# bms_EMBEDDED_R00.net
KiCad netlist of a schematic drawn in Altium Designer
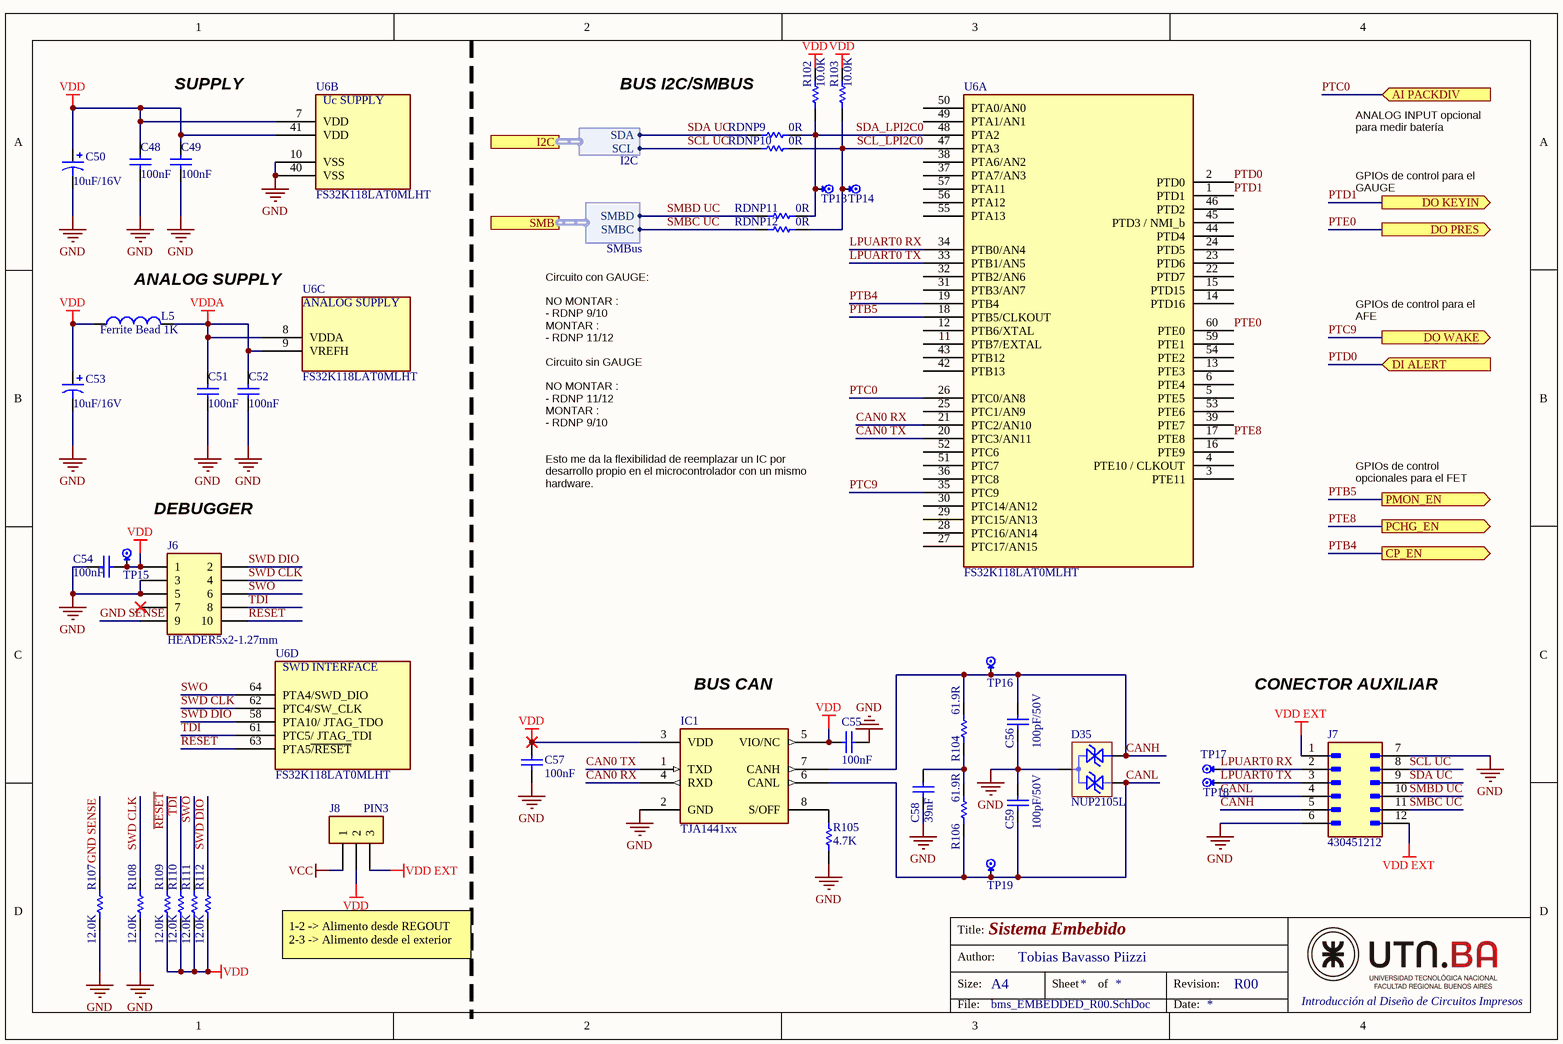
[diagram p0: bms_EMBEDDED_R00.SchDoc]

(export (version "E")
  (design (tool "Eeschema 10.0.6"))
  (components
    (comp (ref "C48")
      (value "100nF")
      (footprint "C0603")
      (description "Capacitor")
      (libsource (lib "capacitors") (part "Cap 0603"))
    )
    (comp (ref "C49")
      (value "100nF")
      (footprint "C0603")
      (description "Capacitor")
      (libsource (lib "capacitors") (part "Cap 0603"))
    )
    (comp (ref "C50")
      (value "10uF/16V")
      (footprint "1206 Cap Tant")
      (description "Polarized Capacitor Tantalium")
      (libsource (lib "capacitors") (part "Cap Pol Tantalio"))
    )
    (comp (ref "C51")
      (value "100nF")
      (footprint "C0603")
      (description "Capacitor")
      (libsource (lib "capacitors") (part "Cap 0603"))
    )
    (comp (ref "C52")
      (value "100nF")
      (footprint "C0603")
      (description "Capacitor")
      (libsource (lib "capacitors") (part "Cap 0603"))
    )
    (comp (ref "C53")
      (value "10uF/16V")
      (footprint "1206 Cap Tant")
      (description "Polarized Capacitor Tantalium")
      (libsource (lib "capacitors") (part "Cap Pol Tantalio"))
    )
    (comp (ref "C54")
      (value "100nF")
      (footprint "C0603")
      (description "Capacitor")
      (libsource (lib "capacitors") (part "Cap 0603"))
    )
    (comp (ref "C55")
      (value "100nF")
      (footprint "C0603")
      (description "Capacitor")
      (libsource (lib "capacitors") (part "Cap 0603"))
    )
    (comp (ref "C56")
      (value "100pF/50V")
      (footprint "C0603")
      (description "Capacitor")
      (libsource (lib "capacitors") (part "Cap 0603"))
    )
    (comp (ref "C57")
      (value "100nF")
      (footprint "C0603")
      (description "Capacitor")
      (libsource (lib "capacitors") (part "Cap 0603"))
    )
    (comp (ref "C58")
      (value "39nF")
      (footprint "C0603")
      (description "Capacitor")
      (libsource (lib "capacitors") (part "Cap 0603"))
    )
    (comp (ref "C59")
      (value "100pF/50V")
      (footprint "C0603")
      (description "Capacitor")
      (libsource (lib "capacitors") (part "Cap 0603"))
    )
    (comp (ref "D35")
      (value "NUP2105L")
      (footprint "SOT-23")
      (description "Dual Line CAN Bus Protector TVS DIODE 24VWM 44VC SOT23-3")
      (libsource (lib "diodes") (part "NUP2105L"))
    )
    (comp (ref "IC1")
      (value "TJA1441xx")
      (footprint "SOIC8")
      (description "High-speed CAN transceiver")
      (libsource (lib "integrated_circuits") (part "TJA1441xx"))
    )
    (comp (ref "J6")
      (value "HEADER5x2-1.27mm")
      (footprint "PAD10-2X05-HH")
      (description "PAD10-2X05-HH")
      (libsource (lib "connectors") (part "HEADER5x2-1.27mm"))
    )
    (comp (ref "J7")
      (value "430451212")
      (footprint "MOLEX_430451212")
      (description "Micro-Fit 3.0 43045\r\nCONN HEADER VERT 12POS 3MM")
      (fields (field (name "MP") "430451012"))
      (libsource (lib "connectors") (part "430451212"))
    )
    (comp (ref "J8") (value "PIN3") (footprint "SIP3") (libsource (lib "connectors") (part "PIN3")))
    (comp (ref "L5")
      (value "Ferrite Bead 1K")
      (footprint "0603 FB")
      (description "BLM18KG102SN1D 1K")
      (libsource (lib "inductors") (part "BLM18KG102SN1D"))
    )
    (comp (ref "R102")
      (value "10.0K")
      (footprint "R0603")
      (description "Resistor")
      (libsource (lib "resistors") (part "Res"))
    )
    (comp (ref "R103")
      (value "10.0K")
      (footprint "R0603")
      (description "Resistor")
      (libsource (lib "resistors") (part "Res"))
    )
    (comp (ref "R104")
      (value "61.9R")
      (footprint "R0603")
      (description "Resistor")
      (libsource (lib "resistors") (part "Res"))
    )
    (comp (ref "R105")
      (value "4.7K")
      (footprint "R0603")
      (description "Resistor")
      (libsource (lib "resistors") (part "Res"))
    )
    (comp (ref "R106")
      (value "61.9R")
      (footprint "R0603")
      (description "Resistor")
      (libsource (lib "resistors") (part "Res"))
    )
    (comp (ref "R107")
      (value "12.0K")
      (footprint "R0603")
      (description "Resistor")
      (libsource (lib "resistors") (part "Res"))
    )
    (comp (ref "R108")
      (value "12.0K")
      (footprint "R0603")
      (description "Resistor")
      (libsource (lib "resistors") (part "Res"))
    )
    (comp (ref "R109")
      (value "12.0K")
      (footprint "R0603")
      (description "Resistor")
      (libsource (lib "resistors") (part "Res"))
    )
    (comp (ref "R110")
      (value "12.0K")
      (footprint "R0603")
      (description "Resistor")
      (libsource (lib "resistors") (part "Res"))
    )
    (comp (ref "R111")
      (value "12.0K")
      (footprint "R0603")
      (description "Resistor")
      (libsource (lib "resistors") (part "Res"))
    )
    (comp (ref "R112")
      (value "12.0K")
      (footprint "R0603")
      (description "Resistor")
      (libsource (lib "resistors") (part "Res"))
    )
    (comp (ref "RDNP9")
      (value "0R")
      (footprint "R0603")
      (description "Resistor")
      (libsource (lib "resistors") (part "Res"))
    )
    (comp (ref "RDNP10")
      (value "0R")
      (footprint "R0603")
      (description "Resistor")
      (libsource (lib "resistors") (part "Res"))
    )
    (comp (ref "RDNP11")
      (value "0R")
      (footprint "R0603")
      (description "Resistor")
      (libsource (lib "resistors") (part "Res"))
    )
    (comp (ref "RDNP12")
      (value "0R")
      (footprint "R0603")
      (description "Resistor")
      (libsource (lib "resistors") (part "Res"))
    )
    (comp (ref "TP13")
      (value "Test Point")
      (footprint "TEST POINT SMD 1")
      (libsource (lib "connectors") (part "Test Point"))
    )
    (comp (ref "TP14")
      (value "Test Point")
      (footprint "TEST POINT SMD 1")
      (libsource (lib "connectors") (part "Test Point"))
    )
    (comp (ref "TP15")
      (value "Test Point")
      (footprint "TEST POINT SMD 1")
      (libsource (lib "connectors") (part "Test Point"))
    )
    (comp (ref "TP16")
      (value "Test Point")
      (footprint "TEST POINT SMD 1")
      (libsource (lib "connectors") (part "Test Point"))
    )
    (comp (ref "TP17")
      (value "Test Point")
      (footprint "TEST POINT SMD 1")
      (libsource (lib "connectors") (part "Test Point"))
    )
    (comp (ref "TP18")
      (value "Test Point")
      (footprint "TEST POINT SMD 1")
      (libsource (lib "connectors") (part "Test Point"))
    )
    (comp (ref "TP19")
      (value "Test Point")
      (footprint "TEST POINT SMD 1")
      (libsource (lib "connectors") (part "Test Point"))
    )
    (comp (ref "U6")
      (value "FS32K118LAT0MLHT")
      (footprint "LQFP64-NXP")
      (libsource (lib "nxp") (part "FS32K118LAT0MLHT"))
    )
  )
  (nets
    (net (code "3") (name "/CAN0 RX") (class "Default")
      (node (ref "IC1") (pin "4") (pinfunction "RXD_4") (pintype "output"))
      (node (ref "U6") (pin "21") (pinfunction "PTC2/AN10_21") (pintype "passive"))
    )
    (net (code "4") (name "/CAN0 TX") (class "Default")
      (node (ref "IC1") (pin "1") (pinfunction "TXD_1") (pintype "input"))
      (node (ref "U6") (pin "20") (pinfunction "PTC3/AN11_20") (pintype "passive"))
    )
    (net (code "5") (name "/CANH") (class "Default")
      (node (ref "C56") (pin "2") (pinfunction "2_2") (pintype "passive"))
      (node (ref "D35") (pin "1") (pinfunction "1_1") (pintype "passive"))
      (node (ref "IC1") (pin "7") (pinfunction "CANH_7") (pintype "output"))
      (node (ref "J7") (pin "5") (pinfunction "5_5") (pintype "passive"))
      (node (ref "R104") (pin "2") (pinfunction "2_2") (pintype "passive"))
      (node (ref "TP16") (pin "1") (pinfunction "1_1") (pintype "passive"))
    )
    (net (code "6") (name "/CANL") (class "Default")
      (node (ref "C59") (pin "1") (pinfunction "1_1") (pintype "passive"))
      (node (ref "D35") (pin "2") (pinfunction "2_2") (pintype "passive"))
      (node (ref "IC1") (pin "6") (pinfunction "CANL_6") (pintype "output"))
      (node (ref "J7") (pin "4") (pinfunction "4_4") (pintype "passive"))
      (node (ref "R106") (pin "1") (pinfunction "1_1") (pintype "passive"))
      (node (ref "TP19") (pin "1") (pinfunction "1_1") (pintype "passive"))
    )
    (net (code "7") (name "/GND SENSE") (class "Default")
      (node (ref "J6") (pin "9") (pinfunction "9_9") (pintype "passive"))
      (node (ref "R107") (pin "1") (pinfunction "1_1") (pintype "passive"))
    )
    (net (code "8") (name "/LPUART0 RX") (class "Default")
      (node (ref "J7") (pin "2") (pinfunction "2_2") (pintype "passive"))
      (node (ref "TP17") (pin "1") (pinfunction "1_1") (pintype "passive"))
      (node (ref "U6") (pin "34") (pinfunction "PTB0/AN4_34") (pintype "passive"))
    )
    (net (code "9") (name "/LPUART0 TX") (class "Default")
      (node (ref "J7") (pin "3") (pinfunction "3_3") (pintype "passive"))
      (node (ref "TP18") (pin "1") (pinfunction "1_1") (pintype "passive"))
      (node (ref "U6") (pin "33") (pinfunction "PTB1/AN5_33") (pintype "passive"))
    )
    (net (code "10") (name "/PTB4") (class "Default")
      (node (ref "U6") (pin "19") (pinfunction "PTB4_19") (pintype "passive"))
    )
    (net (code "11") (name "/PTB5") (class "Default")
      (node (ref "U6") (pin "18") (pinfunction "PTB5/CLKOUT_18") (pintype "passive"))
    )
    (net (code "12") (name "/PTC0") (class "Default")
      (node (ref "U6") (pin "26") (pinfunction "PTC0/AN8_26") (pintype "passive"))
    )
    (net (code "13") (name "/PTC9") (class "Default")
      (node (ref "U6") (pin "35") (pinfunction "PTC9_35") (pintype "passive"))
    )
    (net (code "14") (name "/PTD0") (class "Default")
      (node (ref "U6") (pin "2") (pinfunction "PTD0_2") (pintype "passive"))
    )
    (net (code "15") (name "/PTD1") (class "Default")
      (node (ref "U6") (pin "1") (pinfunction "PTD1_1") (pintype "passive"))
    )
    (net (code "16") (name "/PTE0") (class "Default")
      (node (ref "U6") (pin "60") (pinfunction "PTE0_60") (pintype "passive"))
    )
    (net (code "17") (name "/PTE8") (class "Default")
      (node (ref "U6") (pin "17") (pinfunction "PTE8_17") (pintype "passive"))
    )
    (net (code "18") (name "/SCL UC") (class "Default")
      (node (ref "J7") (pin "8") (pinfunction "8_8") (pintype "passive"))
      (node (ref "RDNP10") (pin "1") (pinfunction "1_1") (pintype "passive"))
    )
    (net (code "19") (name "/SCL_LPI2C0") (class "Default")
      (node (ref "R103") (pin "2") (pinfunction "2_2") (pintype "passive"))
      (node (ref "RDNP10") (pin "2") (pinfunction "2_2") (pintype "passive"))
      (node (ref "RDNP12") (pin "2") (pinfunction "2_2") (pintype "passive"))
      (node (ref "TP14") (pin "1") (pinfunction "1_1") (pintype "passive"))
      (node (ref "U6") (pin "47") (pinfunction "PTA3_47") (pintype "passive"))
    )
    (net (code "20") (name "/SDA UC") (class "Default")
      (node (ref "J7") (pin "9") (pinfunction "9_9") (pintype "passive"))
      (node (ref "RDNP9") (pin "1") (pinfunction "1_1") (pintype "passive"))
    )
    (net (code "21") (name "/SDA_LPI2C0") (class "Default")
      (node (ref "R102") (pin "2") (pinfunction "2_2") (pintype "passive"))
      (node (ref "RDNP11") (pin "2") (pinfunction "2_2") (pintype "passive"))
      (node (ref "RDNP9") (pin "2") (pinfunction "2_2") (pintype "passive"))
      (node (ref "TP13") (pin "1") (pinfunction "1_1") (pintype "passive"))
      (node (ref "U6") (pin "48") (pinfunction "PTA2_48") (pintype "passive"))
    )
    (net (code "22") (name "/SMBC UC") (class "Default")
      (node (ref "J7") (pin "11") (pinfunction "11_11") (pintype "passive"))
      (node (ref "RDNP12") (pin "1") (pinfunction "1_1") (pintype "passive"))
    )
    (net (code "23") (name "/SMBD UC") (class "Default")
      (node (ref "J7") (pin "10") (pinfunction "10_10") (pintype "passive"))
      (node (ref "RDNP11") (pin "1") (pinfunction "1_1") (pintype "passive"))
    )
    (net (code "24") (name "/SWD CLK") (class "Default")
      (node (ref "J6") (pin "4") (pinfunction "4_4") (pintype "passive"))
      (node (ref "R108") (pin "1") (pinfunction "1_1") (pintype "passive"))
      (node (ref "U6") (pin "62") (pinfunction "PTC4/SW_CLK_62") (pintype "passive"))
    )
    (net (code "25") (name "/SWD DIO") (class "Default")
      (node (ref "J6") (pin "2") (pinfunction "2_2") (pintype "passive"))
      (node (ref "R112") (pin "1") (pinfunction "1_1") (pintype "passive"))
      (node (ref "U6") (pin "58") (pinfunction "PTA10/_JTAG_TDO_58") (pintype "passive"))
    )
    (net (code "26") (name "/SWO") (class "Default")
      (node (ref "J6") (pin "6") (pinfunction "6_6") (pintype "passive"))
      (node (ref "R111") (pin "1") (pinfunction "1_1") (pintype "passive"))
      (node (ref "U6") (pin "64") (pinfunction "PTA4/SWD_DIO_64") (pintype "passive"))
    )
    (net (code "27") (name "/TDI") (class "Default")
      (node (ref "J6") (pin "8") (pinfunction "8_8") (pintype "passive"))
      (node (ref "R110") (pin "1") (pinfunction "1_1") (pintype "passive"))
      (node (ref "U6") (pin "61") (pinfunction "PTC5/_JTAG_TDI_61") (pintype "passive"))
    )
    (net (code "30") (name "/~{RESET}") (class "Default")
      (node (ref "J6") (pin "10") (pinfunction "10_10") (pintype "passive"))
      (node (ref "R109") (pin "1") (pinfunction "1_1") (pintype "passive"))
      (node (ref "U6") (pin "63") (pinfunction "PTA5~{/RESET}_63") (pintype "passive"))
    )
    (net (code "31") (name "GND") (class "Default")
      (node (ref "C48") (pin "1") (pinfunction "1_1") (pintype "passive"))
      (node (ref "C49") (pin "1") (pinfunction "1_1") (pintype "passive"))
      (node (ref "C50") (pin "2") (pinfunction "2_2") (pintype "passive"))
      (node (ref "C51") (pin "1") (pinfunction "1_1") (pintype "passive"))
      (node (ref "C52") (pin "1") (pinfunction "1_1") (pintype "passive"))
      (node (ref "C53") (pin "2") (pinfunction "2_2") (pintype "passive"))
      (node (ref "C54") (pin "1") (pinfunction "1_1") (pintype "passive"))
      (node (ref "C55") (pin "1") (pinfunction "1_1") (pintype "passive"))
      (node (ref "C56") (pin "1") (pinfunction "1_1") (pintype "passive"))
      (node (ref "C57") (pin "2") (pinfunction "2_2") (pintype "passive"))
      (node (ref "C58") (pin "1") (pinfunction "1_1") (pintype "passive"))
      (node (ref "C59") (pin "2") (pinfunction "2_2") (pintype "passive"))
      (node (ref "D35") (pin "3") (pinfunction "3_3") (pintype "passive"))
      (node (ref "IC1") (pin "2") (pinfunction "GND_2") (pintype "power_in"))
      (node (ref "J6") (pin "3") (pinfunction "3_3") (pintype "passive"))
      (node (ref "J6") (pin "5") (pinfunction "5_5") (pintype "passive"))
      (node (ref "J7") (pin "6") (pinfunction "6_6") (pintype "passive"))
      (node (ref "J7") (pin "7") (pinfunction "7_7") (pintype "passive"))
      (node (ref "R105") (pin "1") (pinfunction "1_1") (pintype "passive"))
      (node (ref "R107") (pin "2") (pinfunction "2_2") (pintype "passive"))
      (node (ref "R108") (pin "2") (pinfunction "2_2") (pintype "passive"))
      (node (ref "U6") (pin "10") (pinfunction "VSS_10") (pintype "passive"))
      (node (ref "U6") (pin "40") (pinfunction "VSS_40") (pintype "passive"))
    )
    (net (code "32") (name "Net-(C58-Pad2)") (class "Default")
      (node (ref "C58") (pin "2") (pinfunction "2_2") (pintype "passive"))
      (node (ref "R104") (pin "1") (pinfunction "1_1") (pintype "passive"))
      (node (ref "R106") (pin "2") (pinfunction "2_2") (pintype "passive"))
    )
    (net (code "33") (name "Net-(IC1-S{slash}OFF)") (class "Default")
      (node (ref "IC1") (pin "8") (pinfunction "S/OFF_8") (pintype "passive"))
      (node (ref "R105") (pin "2") (pinfunction "2_2") (pintype "passive"))
    )
    (net (code "34") (name "VCC") (class "Default")
      (node (ref "J8") (pin "1") (pinfunction "1_1") (pintype "passive"))
    )
    (net (code "35") (name "VDD") (class "Default")
      (node (ref "C48") (pin "2") (pinfunction "2_2") (pintype "passive"))
      (node (ref "C49") (pin "2") (pinfunction "2_2") (pintype "passive"))
      (node (ref "C50") (pin "1") (pinfunction "1_1") (pintype "passive"))
      (node (ref "C53") (pin "1") (pinfunction "1_1") (pintype "passive"))
      (node (ref "C54") (pin "2") (pinfunction "2_2") (pintype "passive"))
      (node (ref "C55") (pin "2") (pinfunction "2_2") (pintype "passive"))
      (node (ref "C57") (pin "1") (pinfunction "1_1") (pintype "passive"))
      (node (ref "IC1") (pin "3") (pinfunction "VDD_3") (pintype "power_in"))
      (node (ref "IC1") (pin "5") (pinfunction "VIO/NC_5") (pintype "output"))
      (node (ref "J6") (pin "1") (pinfunction "1_1") (pintype "passive"))
      (node (ref "J8") (pin "2") (pinfunction "2_2") (pintype "passive"))
      (node (ref "L5") (pin "1") (pinfunction "1_1") (pintype "passive"))
      (node (ref "R102") (pin "1") (pinfunction "1_1") (pintype "passive"))
      (node (ref "R103") (pin "1") (pinfunction "1_1") (pintype "passive"))
      (node (ref "R109") (pin "2") (pinfunction "2_2") (pintype "passive"))
      (node (ref "R110") (pin "2") (pinfunction "2_2") (pintype "passive"))
      (node (ref "R111") (pin "2") (pinfunction "2_2") (pintype "passive"))
      (node (ref "R112") (pin "2") (pinfunction "2_2") (pintype "passive"))
      (node (ref "TP15") (pin "1") (pinfunction "1_1") (pintype "passive"))
      (node (ref "U6") (pin "41") (pinfunction "VDD_41") (pintype "passive"))
      (node (ref "U6") (pin "7") (pinfunction "VDD_7") (pintype "passive"))
    )
    (net (code "36") (name "VDD EXT") (class "Default")
      (node (ref "J7") (pin "1") (pinfunction "1_1") (pintype "passive"))
      (node (ref "J7") (pin "12") (pinfunction "12_12") (pintype "passive"))
      (node (ref "J8") (pin "3") (pinfunction "3_3") (pintype "passive"))
    )
    (net (code "37") (name "VDDA") (class "Default")
      (node (ref "C51") (pin "2") (pinfunction "2_2") (pintype "passive"))
      (node (ref "C52") (pin "2") (pinfunction "2_2") (pintype "passive"))
      (node (ref "L5") (pin "2") (pinfunction "2_2") (pintype "passive"))
      (node (ref "U6") (pin "8") (pinfunction "VDDA_8") (pintype "passive"))
      (node (ref "U6") (pin "9") (pinfunction "VREFH_9") (pintype "passive"))
    )
    (net (code "38") (name "unconnected-(J6-Pad7)") (class "Default")
      (node (ref "J6") (pin "7") (pinfunction "7_7") (pintype "passive+no_connect"))
    )
    (net (code "39") (name "unconnected-(U6A-PTA0{slash}AN0-Pad50)") (class "Default")
      (node (ref "U6") (pin "50") (pinfunction "PTA0/AN0_50") (pintype "passive"))
    )
    (net (code "40") (name "unconnected-(U6A-PTA1{slash}AN1-Pad49)") (class "Default")
      (node (ref "U6") (pin "49") (pinfunction "PTA1/AN1_49") (pintype "passive"))
    )
    (net (code "41") (name "unconnected-(U6A-PTA6{slash}AN2-Pad38)") (class "Default")
      (node (ref "U6") (pin "38") (pinfunction "PTA6/AN2_38") (pintype "passive"))
    )
    (net (code "42") (name "unconnected-(U6A-PTA7{slash}AN3-Pad37)") (class "Default")
      (node (ref "U6") (pin "37") (pinfunction "PTA7/AN3_37") (pintype "passive"))
    )
    (net (code "43") (name "unconnected-(U6A-PTA11-Pad57)") (class "Default")
      (node (ref "U6") (pin "57") (pinfunction "PTA11_57") (pintype "passive"))
    )
    (net (code "44") (name "unconnected-(U6A-PTA12-Pad56)") (class "Default")
      (node (ref "U6") (pin "56") (pinfunction "PTA12_56") (pintype "passive"))
    )
    (net (code "45") (name "unconnected-(U6A-PTA13-Pad55)") (class "Default")
      (node (ref "U6") (pin "55") (pinfunction "PTA13_55") (pintype "passive"))
    )
    (net (code "46") (name "unconnected-(U6A-PTB2{slash}AN6-Pad32)") (class "Default")
      (node (ref "U6") (pin "32") (pinfunction "PTB2/AN6_32") (pintype "passive"))
    )
    (net (code "47") (name "unconnected-(U6A-PTB3{slash}AN7-Pad31)") (class "Default")
      (node (ref "U6") (pin "31") (pinfunction "PTB3/AN7_31") (pintype "passive"))
    )
    (net (code "48") (name "unconnected-(U6A-PTB6{slash}XTAL-Pad12)") (class "Default")
      (node (ref "U6") (pin "12") (pinfunction "PTB6/XTAL_12") (pintype "passive"))
    )
    (net (code "49") (name "unconnected-(U6A-PTB7{slash}EXTAL-Pad11)") (class "Default")
      (node (ref "U6") (pin "11") (pinfunction "PTB7/EXTAL_11") (pintype "passive"))
    )
    (net (code "50") (name "unconnected-(U6A-PTB12-Pad43)") (class "Default")
      (node (ref "U6") (pin "43") (pinfunction "PTB12_43") (pintype "passive"))
    )
    (net (code "51") (name "unconnected-(U6A-PTB13-Pad42)") (class "Default")
      (node (ref "U6") (pin "42") (pinfunction "PTB13_42") (pintype "passive"))
    )
    (net (code "52") (name "unconnected-(U6A-PTC1{slash}AN9-Pad25)") (class "Default")
      (node (ref "U6") (pin "25") (pinfunction "PTC1/AN9_25") (pintype "passive"))
    )
    (net (code "53") (name "unconnected-(U6A-PTC6-Pad52)") (class "Default")
      (node (ref "U6") (pin "52") (pinfunction "PTC6_52") (pintype "passive"))
    )
    (net (code "54") (name "unconnected-(U6A-PTC7-Pad51)") (class "Default")
      (node (ref "U6") (pin "51") (pinfunction "PTC7_51") (pintype "passive"))
    )
    (net (code "55") (name "unconnected-(U6A-PTC8-Pad36)") (class "Default")
      (node (ref "U6") (pin "36") (pinfunction "PTC8_36") (pintype "passive"))
    )
    (net (code "56") (name "unconnected-(U6A-PTC14{slash}AN12-Pad30)") (class "Default")
      (node (ref "U6") (pin "30") (pinfunction "PTC14/AN12_30") (pintype "passive"))
    )
    (net (code "57") (name "unconnected-(U6A-PTC15{slash}AN13-Pad29)") (class "Default")
      (node (ref "U6") (pin "29") (pinfunction "PTC15/AN13_29") (pintype "passive"))
    )
    (net (code "58") (name "unconnected-(U6A-PTC16{slash}AN14-Pad28)") (class "Default")
      (node (ref "U6") (pin "28") (pinfunction "PTC16/AN14_28") (pintype "passive"))
    )
    (net (code "59") (name "unconnected-(U6A-PTC17{slash}AN15-Pad27)") (class "Default")
      (node (ref "U6") (pin "27") (pinfunction "PTC17/AN15_27") (pintype "passive"))
    )
    (net (code "60") (name "unconnected-(U6A-PTD2-Pad46)") (class "Default")
      (node (ref "U6") (pin "46") (pinfunction "PTD2_46") (pintype "passive"))
    )
    (net (code "61") (name "unconnected-(U6A-PTD3_{slash}_NMI_b-Pad45)") (class "Default")
      (node (ref "U6") (pin "45") (pinfunction "PTD3_/_NMI_b_45") (pintype "passive"))
    )
    (net (code "62") (name "unconnected-(U6A-PTD4-Pad44)") (class "Default")
      (node (ref "U6") (pin "44") (pinfunction "PTD4_44") (pintype "passive"))
    )
    (net (code "63") (name "unconnected-(U6A-PTD5-Pad24)") (class "Default")
      (node (ref "U6") (pin "24") (pinfunction "PTD5_24") (pintype "passive"))
    )
    (net (code "64") (name "unconnected-(U6A-PTD6-Pad23)") (class "Default")
      (node (ref "U6") (pin "23") (pinfunction "PTD6_23") (pintype "passive"))
    )
    (net (code "65") (name "unconnected-(U6A-PTD7-Pad22)") (class "Default")
      (node (ref "U6") (pin "22") (pinfunction "PTD7_22") (pintype "passive"))
    )
    (net (code "66") (name "unconnected-(U6A-PTD15-Pad15)") (class "Default")
      (node (ref "U6") (pin "15") (pinfunction "PTD15_15") (pintype "passive"))
    )
    (net (code "67") (name "unconnected-(U6A-PTD16-Pad14)") (class "Default")
      (node (ref "U6") (pin "14") (pinfunction "PTD16_14") (pintype "passive"))
    )
    (net (code "68") (name "unconnected-(U6A-PTE1-Pad59)") (class "Default")
      (node (ref "U6") (pin "59") (pinfunction "PTE1_59") (pintype "passive"))
    )
    (net (code "69") (name "unconnected-(U6A-PTE2-Pad54)") (class "Default")
      (node (ref "U6") (pin "54") (pinfunction "PTE2_54") (pintype "passive"))
    )
    (net (code "70") (name "unconnected-(U6A-PTE3-Pad13)") (class "Default")
      (node (ref "U6") (pin "13") (pinfunction "PTE3_13") (pintype "passive"))
    )
    (net (code "71") (name "unconnected-(U6A-PTE4-Pad6)") (class "Default")
      (node (ref "U6") (pin "6") (pinfunction "PTE4_6") (pintype "passive"))
    )
    (net (code "72") (name "unconnected-(U6A-PTE5-Pad5)") (class "Default")
      (node (ref "U6") (pin "5") (pinfunction "PTE5_5") (pintype "passive"))
    )
    (net (code "73") (name "unconnected-(U6A-PTE6-Pad53)") (class "Default")
      (node (ref "U6") (pin "53") (pinfunction "PTE6_53") (pintype "passive"))
    )
    (net (code "74") (name "unconnected-(U6A-PTE7-Pad39)") (class "Default")
      (node (ref "U6") (pin "39") (pinfunction "PTE7_39") (pintype "passive"))
    )
    (net (code "75") (name "unconnected-(U6A-PTE9-Pad16)") (class "Default")
      (node (ref "U6") (pin "16") (pinfunction "PTE9_16") (pintype "passive"))
    )
    (net (code "76") (name "unconnected-(U6A-PTE10_{slash}_CLKOUT-Pad4)") (class "Default")
      (node (ref "U6") (pin "4") (pinfunction "PTE10_/_CLKOUT_4") (pintype "passive"))
    )
    (net (code "77") (name "unconnected-(U6A-PTE11-Pad3)") (class "Default")
      (node (ref "U6") (pin "3") (pinfunction "PTE11_3") (pintype "passive"))
    )
  )
)
